# TEC-BVr2.net
KiCad netlist of a schematic drawn in EAGLE
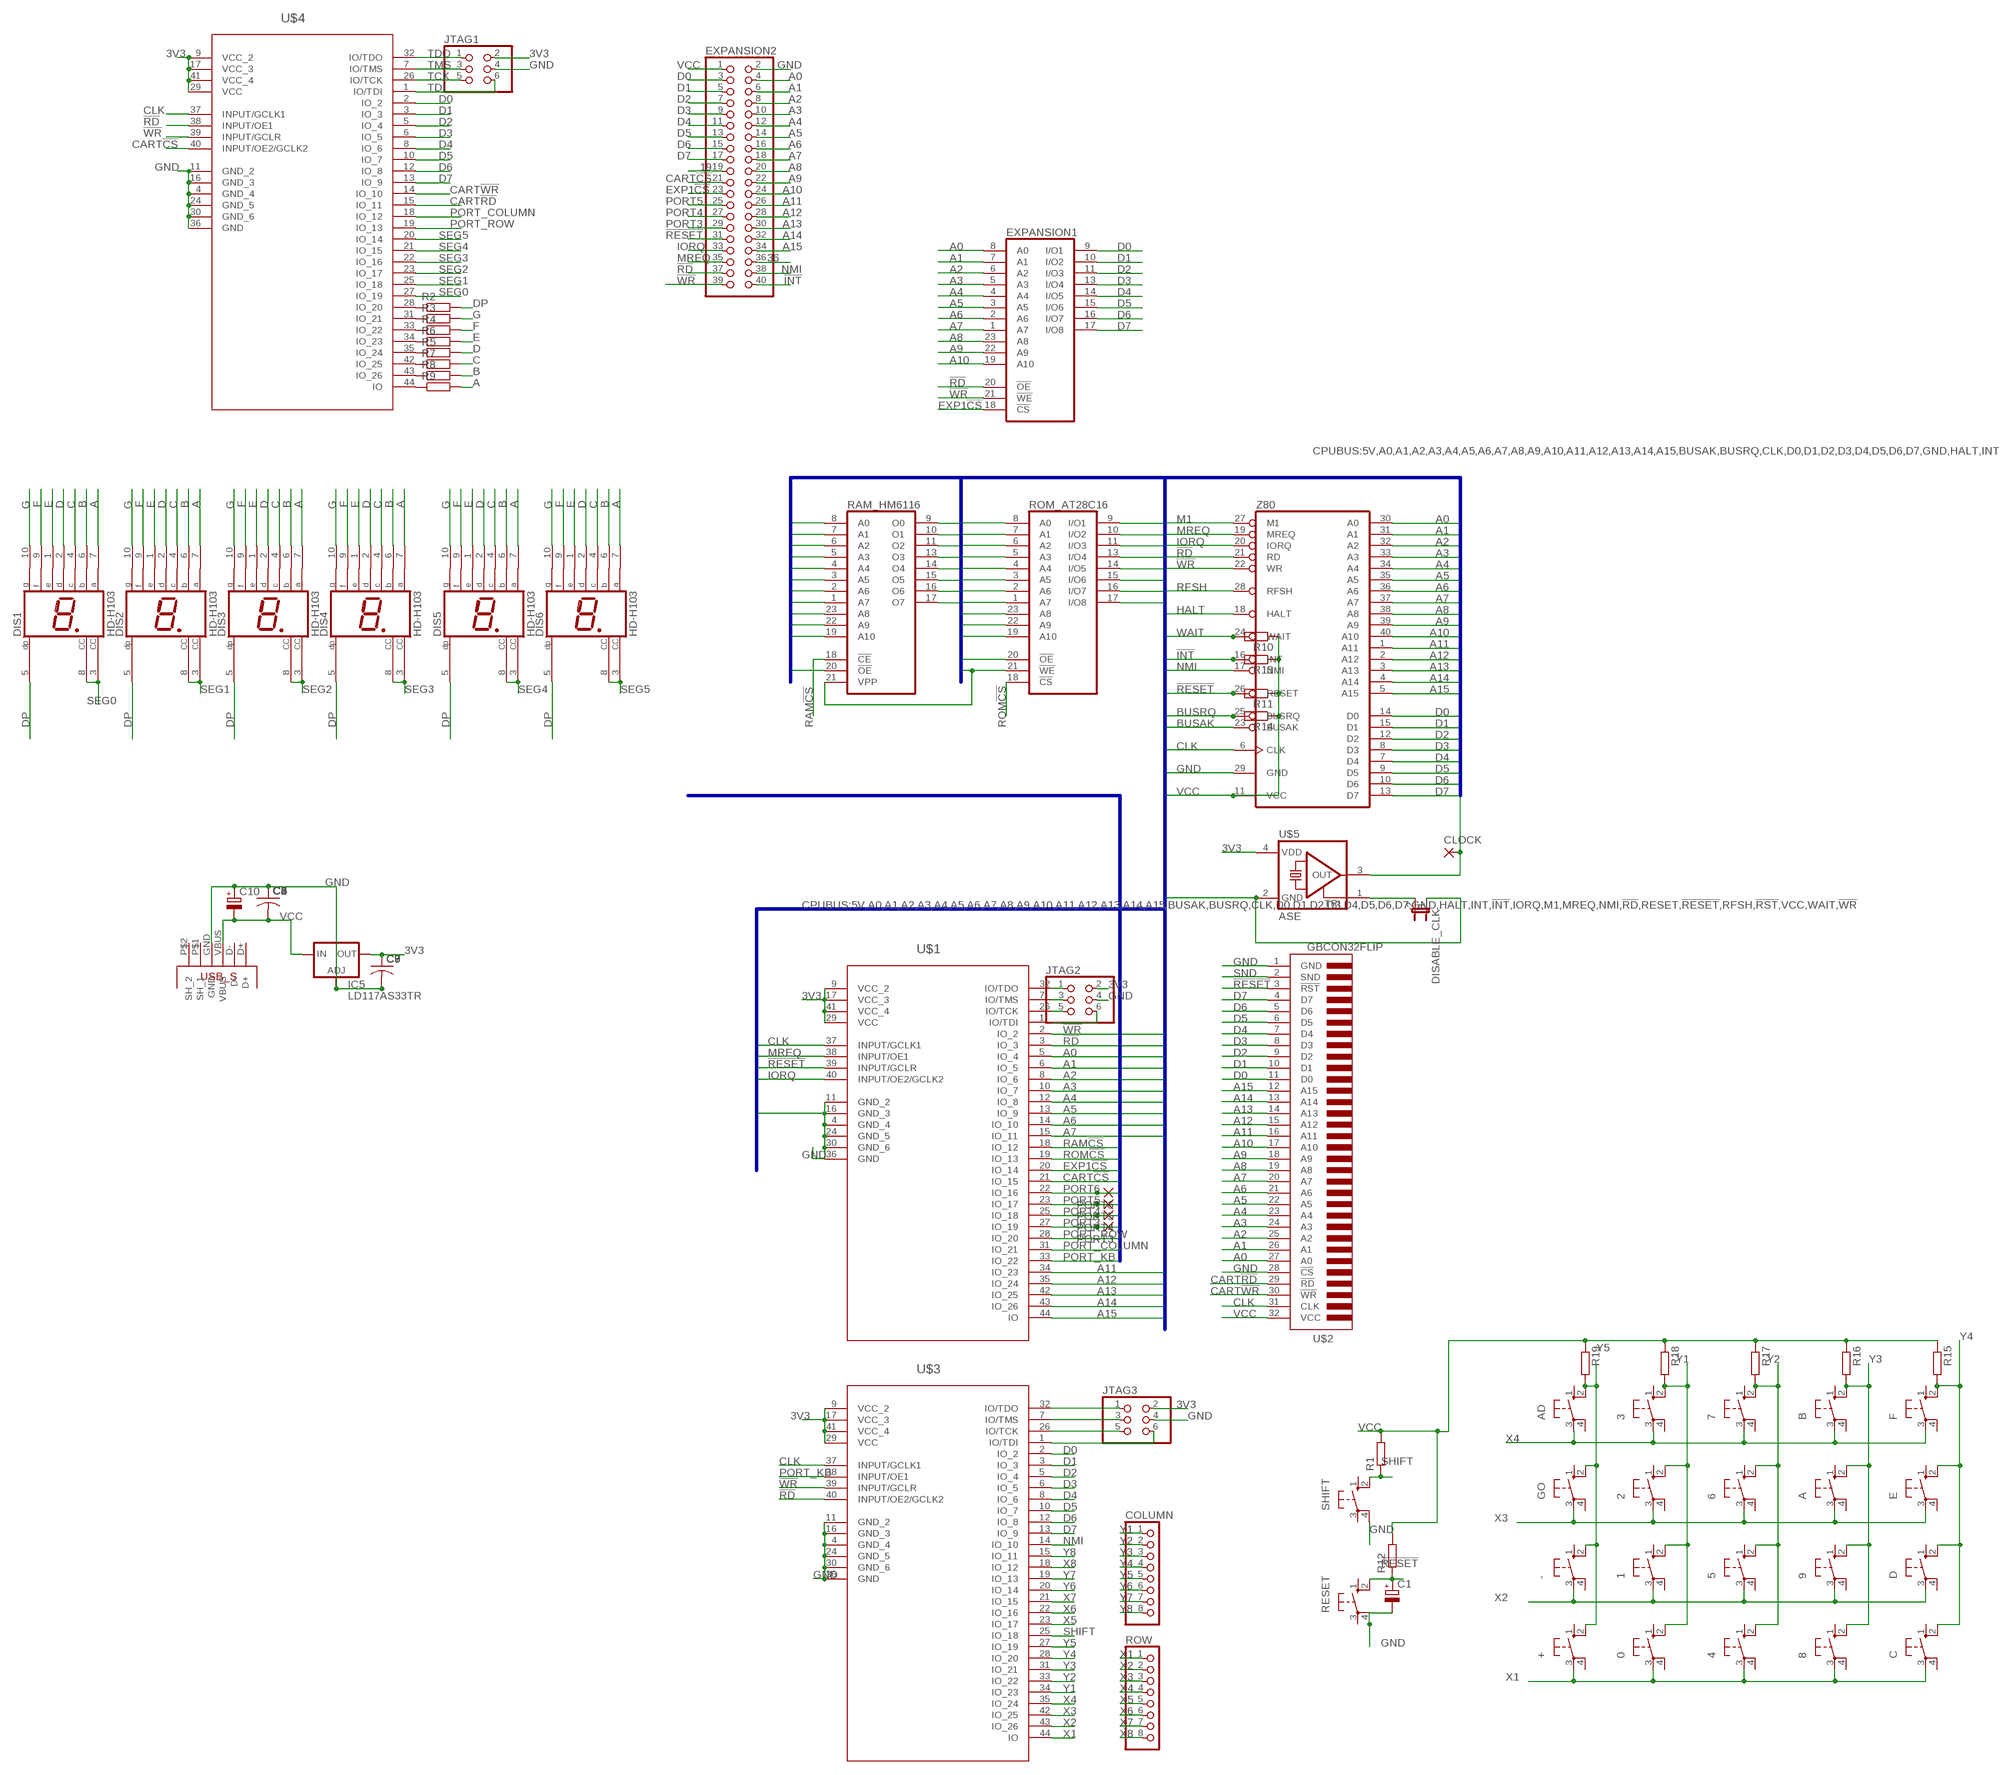
[diagram p0: schematic, sheet 1, part 1 of 2]
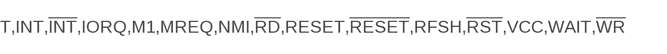
[diagram p1: schematic, sheet 1, part 2 of 2]

(export (version "E")
  (design (tool "Eeschema 10.0.6"))
  (components
    (comp (ref "+")
      (value "10-XX")
      (footprint "eagle-import:B3F-10XX")
      (fields (field (name "MPN") "B3F-1000"))
      (libsource (lib "eagle-import") (part "10-XX"))
    )
    (comp (ref "-")
      (value "10-XX")
      (footprint "eagle-import:B3F-10XX")
      (fields (field (name "MPN") "B3F-1000"))
      (libsource (lib "eagle-import") (part "10-XX"))
    )
    (comp (ref "0")
      (value "10-XX")
      (footprint "eagle-import:B3F-10XX")
      (fields (field (name "MPN") "B3F-1000"))
      (libsource (lib "eagle-import") (part "10-XX"))
    )
    (comp (ref "1")
      (value "10-XX")
      (footprint "eagle-import:B3F-10XX")
      (fields (field (name "MPN") "B3F-1000"))
      (libsource (lib "eagle-import") (part "10-XX"))
    )
    (comp (ref "2")
      (value "10-XX")
      (footprint "eagle-import:B3F-10XX")
      (fields (field (name "MPN") "B3F-1000"))
      (libsource (lib "eagle-import") (part "10-XX"))
    )
    (comp (ref "3")
      (value "10-XX")
      (footprint "eagle-import:B3F-10XX")
      (fields (field (name "MPN") "B3F-1000"))
      (libsource (lib "eagle-import") (part "10-XX"))
    )
    (comp (ref "4")
      (value "10-XX")
      (footprint "eagle-import:B3F-10XX")
      (fields (field (name "MPN") "B3F-1000"))
      (libsource (lib "eagle-import") (part "10-XX"))
    )
    (comp (ref "5")
      (value "10-XX")
      (footprint "eagle-import:B3F-10XX")
      (fields (field (name "MPN") "B3F-1000"))
      (libsource (lib "eagle-import") (part "10-XX"))
    )
    (comp (ref "6")
      (value "10-XX")
      (footprint "eagle-import:B3F-10XX")
      (fields (field (name "MPN") "B3F-1000"))
      (libsource (lib "eagle-import") (part "10-XX"))
    )
    (comp (ref "7")
      (value "10-XX")
      (footprint "eagle-import:B3F-10XX")
      (fields (field (name "MPN") "B3F-1000"))
      (libsource (lib "eagle-import") (part "10-XX"))
    )
    (comp (ref "8")
      (value "10-XX")
      (footprint "eagle-import:B3F-10XX")
      (fields (field (name "MPN") "B3F-1000"))
      (libsource (lib "eagle-import") (part "10-XX"))
    )
    (comp (ref "9")
      (value "10-XX")
      (footprint "eagle-import:B3F-10XX")
      (fields (field (name "MPN") "B3F-1000"))
      (libsource (lib "eagle-import") (part "10-XX"))
    )
    (comp (ref "A")
      (value "10-XX")
      (footprint "eagle-import:B3F-10XX")
      (fields (field (name "MPN") "B3F-1000"))
      (libsource (lib "eagle-import") (part "10-XX"))
    )
    (comp (ref "AD")
      (value "10-XX")
      (footprint "eagle-import:B3F-10XX")
      (fields (field (name "MPN") "B3F-1000"))
      (libsource (lib "eagle-import") (part "10-XX"))
    )
    (comp (ref "B")
      (value "10-XX")
      (footprint "eagle-import:B3F-10XX")
      (fields (field (name "MPN") "B3F-1000"))
      (libsource (lib "eagle-import") (part "10-XX"))
    )
    (comp (ref "C")
      (value "10-XX")
      (footprint "eagle-import:B3F-10XX")
      (fields (field (name "MPN") "B3F-1000"))
      (libsource (lib "eagle-import") (part "10-XX"))
    )
    (comp (ref "C1")
      (value "CPOL-EUE2,5-6E")
      (footprint "eagle-import:E2,5-6E")
      (libsource (lib "eagle-import") (part "CPOL-EUE2,5-6E"))
    )
    (comp (ref "C2")
      (value "C-US050-024X044")
      (footprint "eagle-import:C050-024X044")
      (libsource (lib "eagle-import") (part "C-US050-024X044"))
    )
    (comp (ref "C3")
      (value "C-US050-024X044")
      (footprint "eagle-import:C050-024X044")
      (libsource (lib "eagle-import") (part "C-US050-024X044"))
    )
    (comp (ref "C4")
      (value "C-US050-024X044")
      (footprint "eagle-import:C050-024X044")
      (libsource (lib "eagle-import") (part "C-US050-024X044"))
    )
    (comp (ref "C5")
      (value "C-US050-024X044")
      (footprint "eagle-import:C050-024X044")
      (libsource (lib "eagle-import") (part "C-US050-024X044"))
    )
    (comp (ref "C6")
      (value "C-US050-024X044")
      (footprint "eagle-import:C050-024X044")
      (libsource (lib "eagle-import") (part "C-US050-024X044"))
    )
    (comp (ref "C7")
      (value "C-US050-024X044")
      (footprint "eagle-import:C050-024X044")
      (libsource (lib "eagle-import") (part "C-US050-024X044"))
    )
    (comp (ref "C8")
      (value "C-US050-024X044")
      (footprint "eagle-import:C050-024X044")
      (libsource (lib "eagle-import") (part "C-US050-024X044"))
    )
    (comp (ref "C9")
      (value "C-US050-024X044")
      (footprint "eagle-import:C050-024X044")
      (libsource (lib "eagle-import") (part "C-US050-024X044"))
    )
    (comp (ref "C10")
      (value "CPOL-EUE2,5-6E")
      (footprint "eagle-import:E2,5-6E")
      (libsource (lib "eagle-import") (part "CPOL-EUE2,5-6E"))
    )
    (comp (ref "CLOCK")
      (value "1,6/0,8")
      (footprint "eagle-import:1,6_0,8")
      (libsource (lib "eagle-import") (part "1,6/0,8"))
    )
    (comp (ref "COLUMN")
      (value "PINHD-1X8")
      (footprint "eagle-import:1X08")
      (libsource (lib "eagle-import") (part "PINHD-1X8"))
    )
    (comp (ref "D")
      (value "10-XX")
      (footprint "eagle-import:B3F-10XX")
      (fields (field (name "MPN") "B3F-1000"))
      (libsource (lib "eagle-import") (part "10-XX"))
    )
    (comp (ref "DIS1")
      (value "HD-H103")
      (footprint "eagle-import:HDSP-M")
      (libsource (lib "eagle-import") (part "HD-H103"))
    )
    (comp (ref "DIS2")
      (value "HD-H103")
      (footprint "eagle-import:HDSP-M")
      (libsource (lib "eagle-import") (part "HD-H103"))
    )
    (comp (ref "DIS3")
      (value "HD-H103")
      (footprint "eagle-import:HDSP-M")
      (libsource (lib "eagle-import") (part "HD-H103"))
    )
    (comp (ref "DIS4")
      (value "HD-H103")
      (footprint "eagle-import:HDSP-M")
      (libsource (lib "eagle-import") (part "HD-H103"))
    )
    (comp (ref "DIS5")
      (value "HD-H103")
      (footprint "eagle-import:HDSP-M")
      (libsource (lib "eagle-import") (part "HD-H103"))
    )
    (comp (ref "DIS6")
      (value "HD-H103")
      (footprint "eagle-import:HDSP-M")
      (libsource (lib "eagle-import") (part "HD-H103"))
    )
    (comp (ref "DISABLE_CLK")
      (value "JP1E")
      (footprint "eagle-import:JP1")
      (libsource (lib "eagle-import") (part "JP1E"))
    )
    (comp (ref "E")
      (value "10-XX")
      (footprint "eagle-import:B3F-10XX")
      (fields (field (name "MPN") "B3F-1000"))
      (libsource (lib "eagle-import") (part "10-XX"))
    )
    (comp (ref "EXPANSION1")
      (value "6116P")
      (footprint "eagle-import:DIL24-6")
      (libsource (lib "eagle-import") (part "6116P"))
    )
    (comp (ref "EXPANSION2")
      (value "PINHD-2X20")
      (footprint "eagle-import:2X20")
      (libsource (lib "eagle-import") (part "PINHD-2X20"))
    )
    (comp (ref "F")
      (value "10-XX")
      (footprint "eagle-import:B3F-10XX")
      (fields (field (name "MPN") "B3F-1000"))
      (libsource (lib "eagle-import") (part "10-XX"))
    )
    (comp (ref "GO")
      (value "10-XX")
      (footprint "eagle-import:B3F-10XX")
      (fields (field (name "MPN") "B3F-1000"))
      (libsource (lib "eagle-import") (part "10-XX"))
    )
    (comp (ref "IC5")
      (value "LD117AS33TR")
      (footprint "eagle-import:SOT223")
      (libsource (lib "eagle-import") (part "LD117A?S33TR"))
    )
    (comp (ref "JTAG1")
      (value "PINHD-2X3")
      (footprint "eagle-import:2X03")
      (libsource (lib "eagle-import") (part "PINHD-2X3"))
    )
    (comp (ref "JTAG2")
      (value "PINHD-2X3")
      (footprint "eagle-import:2X03")
      (libsource (lib "eagle-import") (part "PINHD-2X3"))
    )
    (comp (ref "JTAG3")
      (value "PINHD-2X3")
      (footprint "eagle-import:2X03")
      (libsource (lib "eagle-import") (part "PINHD-2X3"))
    )
    (comp (ref "PORT3")
      (value "1,6/0,8")
      (footprint "eagle-import:1,6_0,8")
      (libsource (lib "eagle-import") (part "1,6/0,8"))
    )
    (comp (ref "PORT4")
      (value "1,6/0,8")
      (footprint "eagle-import:1,6_0,8")
      (libsource (lib "eagle-import") (part "1,6/0,8"))
    )
    (comp (ref "PORT5")
      (value "1,6/0,8")
      (footprint "eagle-import:1,6_0,8")
      (libsource (lib "eagle-import") (part "1,6/0,8"))
    )
    (comp (ref "PORT6")
      (value "1,6/0,8")
      (footprint "eagle-import:1,6_0,8")
      (libsource (lib "eagle-import") (part "1,6/0,8"))
    )
    (comp (ref "R1")
      (value "R-EU_0207/12")
      (footprint "eagle-import:0207_12")
      (libsource (lib "eagle-import") (part "R-EU_0207/12"))
    )
    (comp (ref "R2")
      (value "R-EU_0207/12")
      (footprint "eagle-import:0207_12")
      (libsource (lib "eagle-import") (part "R-EU_0207/12"))
    )
    (comp (ref "R3")
      (value "R-EU_0207/12")
      (footprint "eagle-import:0207_12")
      (libsource (lib "eagle-import") (part "R-EU_0207/12"))
    )
    (comp (ref "R4")
      (value "R-EU_0207/12")
      (footprint "eagle-import:0207_12")
      (libsource (lib "eagle-import") (part "R-EU_0207/12"))
    )
    (comp (ref "R5")
      (value "R-EU_0207/12")
      (footprint "eagle-import:0207_12")
      (libsource (lib "eagle-import") (part "R-EU_0207/12"))
    )
    (comp (ref "R6")
      (value "R-EU_0207/12")
      (footprint "eagle-import:0207_12")
      (libsource (lib "eagle-import") (part "R-EU_0207/12"))
    )
    (comp (ref "R7")
      (value "R-EU_0207/12")
      (footprint "eagle-import:0207_12")
      (libsource (lib "eagle-import") (part "R-EU_0207/12"))
    )
    (comp (ref "R8")
      (value "R-EU_0207/12")
      (footprint "eagle-import:0207_12")
      (libsource (lib "eagle-import") (part "R-EU_0207/12"))
    )
    (comp (ref "R9")
      (value "R-EU_0207/12")
      (footprint "eagle-import:0207_12")
      (libsource (lib "eagle-import") (part "R-EU_0207/12"))
    )
    (comp (ref "R10")
      (value "R-EU_0207/12")
      (footprint "eagle-import:0207_12")
      (libsource (lib "eagle-import") (part "R-EU_0207/12"))
    )
    (comp (ref "R11")
      (value "R-EU_0207/12")
      (footprint "eagle-import:0207_12")
      (libsource (lib "eagle-import") (part "R-EU_0207/12"))
    )
    (comp (ref "R12")
      (value "R-EU_0207/12")
      (footprint "eagle-import:0207_12")
      (libsource (lib "eagle-import") (part "R-EU_0207/12"))
    )
    (comp (ref "R13")
      (value "R-EU_0207/12")
      (footprint "eagle-import:0207_12")
      (libsource (lib "eagle-import") (part "R-EU_0207/12"))
    )
    (comp (ref "R14")
      (value "R-EU_0207/12")
      (footprint "eagle-import:0207_12")
      (libsource (lib "eagle-import") (part "R-EU_0207/12"))
    )
    (comp (ref "R15")
      (value "R-EU_0204/7")
      (footprint "eagle-import:0204_7")
      (libsource (lib "eagle-import") (part "R-EU_0204/7"))
    )
    (comp (ref "R16")
      (value "R-EU_0204/7")
      (footprint "eagle-import:0204_7")
      (libsource (lib "eagle-import") (part "R-EU_0204/7"))
    )
    (comp (ref "R17")
      (value "R-EU_0204/7")
      (footprint "eagle-import:0204_7")
      (libsource (lib "eagle-import") (part "R-EU_0204/7"))
    )
    (comp (ref "R18")
      (value "R-EU_0204/7")
      (footprint "eagle-import:0204_7")
      (libsource (lib "eagle-import") (part "R-EU_0204/7"))
    )
    (comp (ref "R19")
      (value "R-EU_0204/7")
      (footprint "eagle-import:0204_7")
      (libsource (lib "eagle-import") (part "R-EU_0204/7"))
    )
    (comp (ref "RAM_HM6116")
      (value "2716")
      (footprint "eagle-import:DIL24")
      (libsource (lib "eagle-import") (part "2716"))
    )
    (comp (ref "RESET")
      (value "10-XX")
      (footprint "eagle-import:B3F-10XX")
      (fields (field (name "MPN") "B3F-1000"))
      (libsource (lib "eagle-import") (part "10-XX"))
    )
    (comp (ref "ROM_AT28C16")
      (value "6116P")
      (footprint "eagle-import:DIL24-6")
      (libsource (lib "eagle-import") (part "6116P"))
    )
    (comp (ref "ROW")
      (value "PINHD-1X8")
      (footprint "eagle-import:1X08")
      (libsource (lib "eagle-import") (part "PINHD-1X8"))
    )
    (comp (ref "SHIFT")
      (value "10-XX")
      (footprint "eagle-import:B3F-10XX")
      (fields (field (name "MPN") "B3F-1000"))
      (libsource (lib "eagle-import") (part "10-XX"))
    )
    (comp (ref "U$1")
      (value "Address Decoding")
      (footprint "eagle-import:QFP80P1200X1200X120-44N")
      (fields (field (name "MPN") "EPM3064ATC44-10N"))
      (libsource (lib "eagle-import") (part "EPM3064ATC44-10N"))
    )
    (comp (ref "U$2")
      (value "GBCON32FLIP")
      (footprint "eagle-import:GB_CON32")
      (libsource (lib "eagle-import") (part "GBCON32FLIP"))
    )
    (comp (ref "U$3")
      (value "Keyboard Decoding")
      (footprint "eagle-import:QFP80P1200X1200X120-44N")
      (fields (field (name "MPN") "EPM3064ATC44-10N"))
      (libsource (lib "eagle-import") (part "EPM3064ATC44-10N"))
    )
    (comp (ref "U$4")
      (value "Display Decoding")
      (footprint "eagle-import:QFP80P1200X1200X120-44N")
      (fields (field (name "MPN") "EPM3064ATC44-10N"))
      (libsource (lib "eagle-import") (part "EPM3064ATC44-10N"))
    )
    (comp (ref "U$5")
      (value "ASE")
      (footprint "eagle-import:ASE")
      (libsource (lib "eagle-import") (part "ASE"))
    )
    (comp (ref "U$6")
      (value "USB")
      (footprint "eagle-import:USB_B_PTH")
      (libsource (lib "eagle-import") (part "USB"))
    )
    (comp (ref "Z80")
      (value "Z80CPU")
      (footprint "eagle-import:DIL40")
      (libsource (lib "eagle-import") (part "Z80CPU"))
    )
  )
  (nets
    (net (code "5") (name "/3V3") (class "Default")
      (node (ref "C7") (pin "1") (pinfunction "1_1") (pintype "passive"))
      (node (ref "C8") (pin "1") (pinfunction "1_1") (pintype "passive"))
      (node (ref "C9") (pin "1") (pinfunction "1_1") (pintype "passive"))
      (node (ref "IC5") (pin "4") (pinfunction "OUT_4") (pintype "passive"))
      (node (ref "JTAG1") (pin "2") (pinfunction "2_2") (pintype "passive"))
      (node (ref "JTAG2") (pin "2") (pinfunction "2_2") (pintype "passive"))
      (node (ref "JTAG3") (pin "2") (pinfunction "2_2") (pintype "passive"))
      (node (ref "U$1") (pin "17") (pinfunction "VCC_3_17") (pintype "power_in"))
      (node (ref "U$1") (pin "29") (pinfunction "VCC_29") (pintype "power_in"))
      (node (ref "U$1") (pin "41") (pinfunction "VCC_4_41") (pintype "power_in"))
      (node (ref "U$1") (pin "9") (pinfunction "VCC_2_9") (pintype "power_in"))
      (node (ref "U$3") (pin "17") (pinfunction "VCC_3_17") (pintype "power_in"))
      (node (ref "U$3") (pin "29") (pinfunction "VCC_29") (pintype "power_in"))
      (node (ref "U$3") (pin "41") (pinfunction "VCC_4_41") (pintype "power_in"))
      (node (ref "U$3") (pin "9") (pinfunction "VCC_2_9") (pintype "power_in"))
      (node (ref "U$4") (pin "17") (pinfunction "VCC_3_17") (pintype "power_in"))
      (node (ref "U$4") (pin "29") (pinfunction "VCC_29") (pintype "power_in"))
      (node (ref "U$4") (pin "41") (pinfunction "VCC_4_41") (pintype "power_in"))
      (node (ref "U$4") (pin "9") (pinfunction "VCC_2_9") (pintype "power_in"))
      (node (ref "U$5") (pin "4") (pinfunction "VDD_4") (pintype "power_in"))
    )
    (net (code "6") (name "/19") (class "Default")
      (node (ref "EXPANSION2") (pin "19") (pinfunction "19_19") (pintype "passive"))
    )
    (net (code "7") (name "/36") (class "Default")
      (node (ref "EXPANSION2") (pin "36") (pinfunction "36_36") (pintype "passive"))
    )
    (net (code "8") (name "/A") (class "Default")
      (node (ref "DIS1") (pin "7") (pinfunction "A_7") (pintype "passive"))
      (node (ref "DIS2") (pin "7") (pinfunction "A_7") (pintype "passive"))
      (node (ref "DIS3") (pin "7") (pinfunction "A_7") (pintype "passive"))
      (node (ref "DIS4") (pin "7") (pinfunction "A_7") (pintype "passive"))
      (node (ref "DIS5") (pin "7") (pinfunction "A_7") (pintype "passive"))
      (node (ref "DIS6") (pin "7") (pinfunction "A_7") (pintype "passive"))
      (node (ref "R9") (pin "2") (pinfunction "2_2") (pintype "passive"))
    )
    (net (code "9") (name "/A0") (class "Default")
      (node (ref "EXPANSION1") (pin "8") (pinfunction "A0_8") (pintype "input"))
      (node (ref "EXPANSION2") (pin "4") (pinfunction "4_4") (pintype "passive"))
      (node (ref "RAM_HM6116") (pin "8") (pinfunction "A0_8") (pintype "input"))
      (node (ref "ROM_AT28C16") (pin "8") (pinfunction "A0_8") (pintype "input"))
      (node (ref "U$1") (pin "5") (pinfunction "IO_4_5") (pintype "bidirectional"))
      (node (ref "U$2") (pin "27") (pinfunction "A0_27") (pintype "input"))
      (node (ref "Z80") (pin "30") (pinfunction "A0_30") (pintype "output"))
    )
    (net (code "10") (name "/A1") (class "Default")
      (node (ref "EXPANSION1") (pin "7") (pinfunction "A1_7") (pintype "input"))
      (node (ref "EXPANSION2") (pin "6") (pinfunction "6_6") (pintype "passive"))
      (node (ref "RAM_HM6116") (pin "7") (pinfunction "A1_7") (pintype "input"))
      (node (ref "ROM_AT28C16") (pin "7") (pinfunction "A1_7") (pintype "input"))
      (node (ref "U$1") (pin "6") (pinfunction "IO_5_6") (pintype "bidirectional"))
      (node (ref "U$2") (pin "26") (pinfunction "A1_26") (pintype "input"))
      (node (ref "Z80") (pin "31") (pinfunction "A1_31") (pintype "output"))
    )
    (net (code "11") (name "/A2") (class "Default")
      (node (ref "EXPANSION1") (pin "6") (pinfunction "A2_6") (pintype "input"))
      (node (ref "EXPANSION2") (pin "8") (pinfunction "8_8") (pintype "passive"))
      (node (ref "RAM_HM6116") (pin "6") (pinfunction "A2_6") (pintype "input"))
      (node (ref "ROM_AT28C16") (pin "6") (pinfunction "A2_6") (pintype "input"))
      (node (ref "U$1") (pin "8") (pinfunction "IO_6_8") (pintype "bidirectional"))
      (node (ref "U$2") (pin "25") (pinfunction "A2_25") (pintype "input"))
      (node (ref "Z80") (pin "32") (pinfunction "A2_32") (pintype "output"))
    )
    (net (code "12") (name "/A3") (class "Default")
      (node (ref "EXPANSION1") (pin "5") (pinfunction "A3_5") (pintype "input"))
      (node (ref "EXPANSION2") (pin "10") (pinfunction "10_10") (pintype "passive"))
      (node (ref "RAM_HM6116") (pin "5") (pinfunction "A3_5") (pintype "input"))
      (node (ref "ROM_AT28C16") (pin "5") (pinfunction "A3_5") (pintype "input"))
      (node (ref "U$1") (pin "10") (pinfunction "IO_7_10") (pintype "bidirectional"))
      (node (ref "U$2") (pin "24") (pinfunction "A3_24") (pintype "input"))
      (node (ref "Z80") (pin "33") (pinfunction "A3_33") (pintype "output"))
    )
    (net (code "13") (name "/A4") (class "Default")
      (node (ref "EXPANSION1") (pin "4") (pinfunction "A4_4") (pintype "input"))
      (node (ref "EXPANSION2") (pin "12") (pinfunction "12_12") (pintype "passive"))
      (node (ref "RAM_HM6116") (pin "4") (pinfunction "A4_4") (pintype "input"))
      (node (ref "ROM_AT28C16") (pin "4") (pinfunction "A4_4") (pintype "input"))
      (node (ref "U$1") (pin "12") (pinfunction "IO_8_12") (pintype "bidirectional"))
      (node (ref "U$2") (pin "23") (pinfunction "A4_23") (pintype "input"))
      (node (ref "Z80") (pin "34") (pinfunction "A4_34") (pintype "output"))
    )
    (net (code "14") (name "/A5") (class "Default")
      (node (ref "EXPANSION1") (pin "3") (pinfunction "A5_3") (pintype "input"))
      (node (ref "EXPANSION2") (pin "14") (pinfunction "14_14") (pintype "passive"))
      (node (ref "RAM_HM6116") (pin "3") (pinfunction "A5_3") (pintype "input"))
      (node (ref "ROM_AT28C16") (pin "3") (pinfunction "A5_3") (pintype "input"))
      (node (ref "U$1") (pin "13") (pinfunction "IO_9_13") (pintype "bidirectional"))
      (node (ref "U$2") (pin "22") (pinfunction "A5_22") (pintype "input"))
      (node (ref "Z80") (pin "35") (pinfunction "A5_35") (pintype "output"))
    )
    (net (code "15") (name "/A6") (class "Default")
      (node (ref "EXPANSION1") (pin "2") (pinfunction "A6_2") (pintype "input"))
      (node (ref "EXPANSION2") (pin "16") (pinfunction "16_16") (pintype "passive"))
      (node (ref "RAM_HM6116") (pin "2") (pinfunction "A6_2") (pintype "input"))
      (node (ref "ROM_AT28C16") (pin "2") (pinfunction "A6_2") (pintype "input"))
      (node (ref "U$1") (pin "14") (pinfunction "IO_10_14") (pintype "bidirectional"))
      (node (ref "U$2") (pin "21") (pinfunction "A6_21") (pintype "input"))
      (node (ref "Z80") (pin "36") (pinfunction "A6_36") (pintype "output"))
    )
    (net (code "16") (name "/A7") (class "Default")
      (node (ref "EXPANSION1") (pin "1") (pinfunction "A7_1") (pintype "input"))
      (node (ref "EXPANSION2") (pin "18") (pinfunction "18_18") (pintype "passive"))
      (node (ref "RAM_HM6116") (pin "1") (pinfunction "A7_1") (pintype "input"))
      (node (ref "ROM_AT28C16") (pin "1") (pinfunction "A7_1") (pintype "input"))
      (node (ref "U$1") (pin "15") (pinfunction "IO_11_15") (pintype "bidirectional"))
      (node (ref "U$2") (pin "20") (pinfunction "A7_20") (pintype "input"))
      (node (ref "Z80") (pin "37") (pinfunction "A7_37") (pintype "output"))
    )
    (net (code "17") (name "/A8") (class "Default")
      (node (ref "EXPANSION1") (pin "23") (pinfunction "A8_23") (pintype "input"))
      (node (ref "EXPANSION2") (pin "20") (pinfunction "20_20") (pintype "passive"))
      (node (ref "RAM_HM6116") (pin "23") (pinfunction "A8_23") (pintype "input"))
      (node (ref "ROM_AT28C16") (pin "23") (pinfunction "A8_23") (pintype "input"))
      (node (ref "U$2") (pin "19") (pinfunction "A8_19") (pintype "input"))
      (node (ref "Z80") (pin "38") (pinfunction "A8_38") (pintype "output"))
    )
    (net (code "18") (name "/A9") (class "Default")
      (node (ref "EXPANSION1") (pin "22") (pinfunction "A9_22") (pintype "input"))
      (node (ref "EXPANSION2") (pin "22") (pinfunction "22_22") (pintype "passive"))
      (node (ref "RAM_HM6116") (pin "22") (pinfunction "A9_22") (pintype "input"))
      (node (ref "ROM_AT28C16") (pin "22") (pinfunction "A9_22") (pintype "input"))
      (node (ref "U$2") (pin "18") (pinfunction "A9_18") (pintype "input"))
      (node (ref "Z80") (pin "39") (pinfunction "A9_39") (pintype "output"))
    )
    (net (code "19") (name "/A10") (class "Default")
      (node (ref "EXPANSION1") (pin "19") (pinfunction "A10_19") (pintype "input"))
      (node (ref "EXPANSION2") (pin "24") (pinfunction "24_24") (pintype "passive"))
      (node (ref "RAM_HM6116") (pin "19") (pinfunction "A10_19") (pintype "input"))
      (node (ref "ROM_AT28C16") (pin "19") (pinfunction "A10_19") (pintype "input"))
      (node (ref "U$2") (pin "17") (pinfunction "A10_17") (pintype "input"))
      (node (ref "Z80") (pin "40") (pinfunction "A10_40") (pintype "output"))
    )
    (net (code "20") (name "/A11") (class "Default")
      (node (ref "EXPANSION2") (pin "26") (pinfunction "26_26") (pintype "passive"))
      (node (ref "U$1") (pin "34") (pinfunction "IO_23_34") (pintype "bidirectional"))
      (node (ref "U$2") (pin "16") (pinfunction "A11_16") (pintype "input"))
      (node (ref "Z80") (pin "1") (pinfunction "A11_1") (pintype "output"))
    )
    (net (code "21") (name "/A12") (class "Default")
      (node (ref "EXPANSION2") (pin "28") (pinfunction "28_28") (pintype "passive"))
      (node (ref "U$1") (pin "35") (pinfunction "IO_24_35") (pintype "bidirectional"))
      (node (ref "U$2") (pin "15") (pinfunction "A12_15") (pintype "input"))
      (node (ref "Z80") (pin "2") (pinfunction "A12_2") (pintype "output"))
    )
    (net (code "22") (name "/A13") (class "Default")
      (node (ref "EXPANSION2") (pin "30") (pinfunction "30_30") (pintype "passive"))
      (node (ref "U$1") (pin "42") (pinfunction "IO_25_42") (pintype "bidirectional"))
      (node (ref "U$2") (pin "14") (pinfunction "A13_14") (pintype "input"))
      (node (ref "Z80") (pin "3") (pinfunction "A13_3") (pintype "output"))
    )
    (net (code "23") (name "/A14") (class "Default")
      (node (ref "EXPANSION2") (pin "32") (pinfunction "32_32") (pintype "passive"))
      (node (ref "U$1") (pin "43") (pinfunction "IO_26_43") (pintype "bidirectional"))
      (node (ref "U$2") (pin "13") (pinfunction "A14_13") (pintype "input"))
      (node (ref "Z80") (pin "4") (pinfunction "A14_4") (pintype "output"))
    )
    (net (code "24") (name "/A15") (class "Default")
      (node (ref "EXPANSION2") (pin "34") (pinfunction "34_34") (pintype "passive"))
      (node (ref "U$1") (pin "44") (pinfunction "IO_44") (pintype "bidirectional"))
      (node (ref "U$2") (pin "12") (pinfunction "A15_12") (pintype "input"))
      (node (ref "Z80") (pin "5") (pinfunction "A15_5") (pintype "output"))
    )
    (net (code "25") (name "/B") (class "Default")
      (node (ref "DIS1") (pin "6") (pinfunction "B_6") (pintype "passive"))
      (node (ref "DIS2") (pin "6") (pinfunction "B_6") (pintype "passive"))
      (node (ref "DIS3") (pin "6") (pinfunction "B_6") (pintype "passive"))
      (node (ref "DIS4") (pin "6") (pinfunction "B_6") (pintype "passive"))
      (node (ref "DIS5") (pin "6") (pinfunction "B_6") (pintype "passive"))
      (node (ref "DIS6") (pin "6") (pinfunction "B_6") (pintype "passive"))
      (node (ref "R8") (pin "2") (pinfunction "2_2") (pintype "passive"))
    )
    (net (code "26") (name "/BUSAK") (class "Default")
      (node (ref "Z80") (pin "23") (pinfunction "BUSAK_23") (pintype "output"))
    )
    (net (code "27") (name "/BUSRQ") (class "Default")
      (node (ref "R14") (pin "2") (pinfunction "2_2") (pintype "passive"))
      (node (ref "Z80") (pin "25") (pinfunction "BUSRQ_25") (pintype "input"))
    )
    (net (code "28") (name "/C") (class "Default")
      (node (ref "DIS1") (pin "4") (pinfunction "C_4") (pintype "passive"))
      (node (ref "DIS2") (pin "4") (pinfunction "C_4") (pintype "passive"))
      (node (ref "DIS3") (pin "4") (pinfunction "C_4") (pintype "passive"))
      (node (ref "DIS4") (pin "4") (pinfunction "C_4") (pintype "passive"))
      (node (ref "DIS5") (pin "4") (pinfunction "C_4") (pintype "passive"))
      (node (ref "DIS6") (pin "4") (pinfunction "C_4") (pintype "passive"))
      (node (ref "R7") (pin "2") (pinfunction "2_2") (pintype "passive"))
    )
    (net (code "29") (name "/CART~{CS}") (class "Default")
      (node (ref "EXPANSION2") (pin "21") (pinfunction "21_21") (pintype "passive"))
      (node (ref "U$1") (pin "21") (pinfunction "IO_15_21") (pintype "bidirectional"))
      (node (ref "U$4") (pin "40") (pinfunction "INPUT/OE2/GCLK2_40") (pintype "input"))
    )
    (net (code "30") (name "/CART~{RD}") (class "Default")
      (node (ref "U$2") (pin "29") (pinfunction "~{RD}_29") (pintype "input"))
      (node (ref "U$4") (pin "15") (pinfunction "IO_11_15") (pintype "bidirectional"))
    )
    (net (code "31") (name "/CART~{WR}") (class "Default")
      (node (ref "U$2") (pin "30") (pinfunction "~{WR}_30") (pintype "input"))
      (node (ref "U$4") (pin "14") (pinfunction "IO_10_14") (pintype "bidirectional"))
    )
    (net (code "32") (name "/CLK") (class "Default")
      (node (ref "CLOCK") (pin "1") (pinfunction "P_1") (pintype "passive"))
      (node (ref "U$1") (pin "37") (pinfunction "INPUT/GCLK1_37") (pintype "input"))
      (node (ref "U$2") (pin "31") (pinfunction "CLK_31") (pintype "input"))
      (node (ref "U$3") (pin "37") (pinfunction "INPUT/GCLK1_37") (pintype "input"))
      (node (ref "U$4") (pin "37") (pinfunction "INPUT/GCLK1_37") (pintype "input"))
      (node (ref "U$5") (pin "3") (pinfunction "OUT_3") (pintype "output"))
      (node (ref "Z80") (pin "6") (pinfunction "CLK_6") (pintype "input"))
    )
    (net (code "33") (name "/D") (class "Default")
      (node (ref "DIS1") (pin "2") (pinfunction "D_2") (pintype "passive"))
      (node (ref "DIS2") (pin "2") (pinfunction "D_2") (pintype "passive"))
      (node (ref "DIS3") (pin "2") (pinfunction "D_2") (pintype "passive"))
      (node (ref "DIS4") (pin "2") (pinfunction "D_2") (pintype "passive"))
      (node (ref "DIS5") (pin "2") (pinfunction "D_2") (pintype "passive"))
      (node (ref "DIS6") (pin "2") (pinfunction "D_2") (pintype "passive"))
      (node (ref "R5") (pin "2") (pinfunction "2_2") (pintype "passive"))
    )
    (net (code "34") (name "/D0") (class "Default")
      (node (ref "EXPANSION1") (pin "9") (pinfunction "I/O1_9") (pintype "bidirectional"))
      (node (ref "EXPANSION2") (pin "3") (pinfunction "3_3") (pintype "passive"))
      (node (ref "RAM_HM6116") (pin "9") (pinfunction "O0_9") (pintype "tri_state"))
      (node (ref "ROM_AT28C16") (pin "9") (pinfunction "I/O1_9") (pintype "bidirectional"))
      (node (ref "U$2") (pin "11") (pinfunction "D0_11") (pintype "bidirectional"))
      (node (ref "U$3") (pin "2") (pinfunction "IO_2_2") (pintype "bidirectional"))
      (node (ref "U$4") (pin "2") (pinfunction "IO_2_2") (pintype "bidirectional"))
      (node (ref "Z80") (pin "14") (pinfunction "D0_14") (pintype "bidirectional"))
    )
    (net (code "35") (name "/D1") (class "Default")
      (node (ref "EXPANSION1") (pin "10") (pinfunction "I/O2_10") (pintype "bidirectional"))
      (node (ref "EXPANSION2") (pin "5") (pinfunction "5_5") (pintype "passive"))
      (node (ref "RAM_HM6116") (pin "10") (pinfunction "O1_10") (pintype "tri_state"))
      (node (ref "ROM_AT28C16") (pin "10") (pinfunction "I/O2_10") (pintype "bidirectional"))
      (node (ref "U$2") (pin "10") (pinfunction "D1_10") (pintype "bidirectional"))
      (node (ref "U$3") (pin "3") (pinfunction "IO_3_3") (pintype "bidirectional"))
      (node (ref "U$4") (pin "3") (pinfunction "IO_3_3") (pintype "bidirectional"))
      (node (ref "Z80") (pin "15") (pinfunction "D1_15") (pintype "bidirectional"))
    )
    (net (code "36") (name "/D2") (class "Default")
      (node (ref "EXPANSION1") (pin "11") (pinfunction "I/O3_11") (pintype "bidirectional"))
      (node (ref "EXPANSION2") (pin "7") (pinfunction "7_7") (pintype "passive"))
      (node (ref "RAM_HM6116") (pin "11") (pinfunction "O2_11") (pintype "tri_state"))
      (node (ref "ROM_AT28C16") (pin "11") (pinfunction "I/O3_11") (pintype "bidirectional"))
      (node (ref "U$2") (pin "9") (pinfunction "D2_9") (pintype "bidirectional"))
      (node (ref "U$3") (pin "5") (pinfunction "IO_4_5") (pintype "bidirectional"))
      (node (ref "U$4") (pin "5") (pinfunction "IO_4_5") (pintype "bidirectional"))
      (node (ref "Z80") (pin "12") (pinfunction "D2_12") (pintype "bidirectional"))
    )
    (net (code "37") (name "/D3") (class "Default")
      (node (ref "EXPANSION1") (pin "13") (pinfunction "I/O4_13") (pintype "bidirectional"))
      (node (ref "EXPANSION2") (pin "9") (pinfunction "9_9") (pintype "passive"))
      (node (ref "RAM_HM6116") (pin "13") (pinfunction "O3_13") (pintype "tri_state"))
      (node (ref "ROM_AT28C16") (pin "13") (pinfunction "I/O4_13") (pintype "bidirectional"))
      (node (ref "U$2") (pin "8") (pinfunction "D3_8") (pintype "bidirectional"))
      (node (ref "U$3") (pin "6") (pinfunction "IO_5_6") (pintype "bidirectional"))
      (node (ref "U$4") (pin "6") (pinfunction "IO_5_6") (pintype "bidirectional"))
      (node (ref "Z80") (pin "8") (pinfunction "D3_8") (pintype "bidirectional"))
    )
    (net (code "38") (name "/D4") (class "Default")
      (node (ref "EXPANSION1") (pin "14") (pinfunction "I/O5_14") (pintype "bidirectional"))
      (node (ref "EXPANSION2") (pin "11") (pinfunction "11_11") (pintype "passive"))
      (node (ref "RAM_HM6116") (pin "14") (pinfunction "O4_14") (pintype "tri_state"))
      (node (ref "ROM_AT28C16") (pin "14") (pinfunction "I/O5_14") (pintype "bidirectional"))
      (node (ref "U$2") (pin "7") (pinfunction "D4_7") (pintype "bidirectional"))
      (node (ref "U$3") (pin "8") (pinfunction "IO_6_8") (pintype "bidirectional"))
      (node (ref "U$4") (pin "8") (pinfunction "IO_6_8") (pintype "bidirectional"))
      (node (ref "Z80") (pin "7") (pinfunction "D4_7") (pintype "bidirectional"))
    )
    (net (code "39") (name "/D5") (class "Default")
      (node (ref "EXPANSION1") (pin "15") (pinfunction "I/O6_15") (pintype "bidirectional"))
      (node (ref "EXPANSION2") (pin "13") (pinfunction "13_13") (pintype "passive"))
      (node (ref "RAM_HM6116") (pin "15") (pinfunction "O5_15") (pintype "tri_state"))
      (node (ref "ROM_AT28C16") (pin "15") (pinfunction "I/O6_15") (pintype "bidirectional"))
      (node (ref "U$2") (pin "6") (pinfunction "D5_6") (pintype "bidirectional"))
      (node (ref "U$3") (pin "10") (pinfunction "IO_7_10") (pintype "bidirectional"))
      (node (ref "U$4") (pin "10") (pinfunction "IO_7_10") (pintype "bidirectional"))
      (node (ref "Z80") (pin "9") (pinfunction "D5_9") (pintype "bidirectional"))
    )
    (net (code "40") (name "/D6") (class "Default")
      (node (ref "EXPANSION1") (pin "16") (pinfunction "I/O7_16") (pintype "bidirectional"))
      (node (ref "EXPANSION2") (pin "15") (pinfunction "15_15") (pintype "passive"))
      (node (ref "RAM_HM6116") (pin "16") (pinfunction "O6_16") (pintype "tri_state"))
      (node (ref "ROM_AT28C16") (pin "16") (pinfunction "I/O7_16") (pintype "bidirectional"))
      (node (ref "U$2") (pin "5") (pinfunction "D6_5") (pintype "bidirectional"))
      (node (ref "U$3") (pin "12") (pinfunction "IO_8_12") (pintype "bidirectional"))
      (node (ref "U$4") (pin "12") (pinfunction "IO_8_12") (pintype "bidirectional"))
      (node (ref "Z80") (pin "10") (pinfunction "D6_10") (pintype "bidirectional"))
    )
    (net (code "41") (name "/D7") (class "Default")
      (node (ref "EXPANSION1") (pin "17") (pinfunction "I/O8_17") (pintype "bidirectional"))
      (node (ref "EXPANSION2") (pin "17") (pinfunction "17_17") (pintype "passive"))
      (node (ref "RAM_HM6116") (pin "17") (pinfunction "O7_17") (pintype "tri_state"))
      (node (ref "ROM_AT28C16") (pin "17") (pinfunction "I/O8_17") (pintype "bidirectional"))
      (node (ref "U$2") (pin "4") (pinfunction "D7_4") (pintype "bidirectional"))
      (node (ref "U$3") (pin "13") (pinfunction "IO_9_13") (pintype "bidirectional"))
      (node (ref "U$4") (pin "13") (pinfunction "IO_9_13") (pintype "bidirectional"))
      (node (ref "Z80") (pin "13") (pinfunction "D7_13") (pintype "bidirectional"))
    )
    (net (code "42") (name "/DP") (class "Default")
      (node (ref "DIS1") (pin "5") (pinfunction "DP_5") (pintype "passive"))
      (node (ref "DIS2") (pin "5") (pinfunction "DP_5") (pintype "passive"))
      (node (ref "DIS3") (pin "5") (pinfunction "DP_5") (pintype "passive"))
      (node (ref "DIS4") (pin "5") (pinfunction "DP_5") (pintype "passive"))
      (node (ref "DIS5") (pin "5") (pinfunction "DP_5") (pintype "passive"))
      (node (ref "DIS6") (pin "5") (pinfunction "DP_5") (pintype "passive"))
      (node (ref "R2") (pin "2") (pinfunction "2_2") (pintype "passive"))
    )
    (net (code "43") (name "/E") (class "Default")
      (node (ref "DIS1") (pin "1") (pinfunction "E_1") (pintype "passive"))
      (node (ref "DIS2") (pin "1") (pinfunction "E_1") (pintype "passive"))
      (node (ref "DIS3") (pin "1") (pinfunction "E_1") (pintype "passive"))
      (node (ref "DIS4") (pin "1") (pinfunction "E_1") (pintype "passive"))
      (node (ref "DIS5") (pin "1") (pinfunction "E_1") (pintype "passive"))
      (node (ref "DIS6") (pin "1") (pinfunction "E_1") (pintype "passive"))
      (node (ref "R6") (pin "2") (pinfunction "2_2") (pintype "passive"))
    )
    (net (code "44") (name "/EXP1~{CS}") (class "Default")
      (node (ref "EXPANSION1") (pin "18") (pinfunction "~{CS}_18") (pintype "input"))
      (node (ref "EXPANSION2") (pin "23") (pinfunction "23_23") (pintype "passive"))
      (node (ref "U$1") (pin "20") (pinfunction "IO_14_20") (pintype "bidirectional"))
    )
    (net (code "45") (name "/F") (class "Default")
      (node (ref "DIS1") (pin "9") (pinfunction "F_9") (pintype "passive"))
      (node (ref "DIS2") (pin "9") (pinfunction "F_9") (pintype "passive"))
      (node (ref "DIS3") (pin "9") (pinfunction "F_9") (pintype "passive"))
      (node (ref "DIS4") (pin "9") (pinfunction "F_9") (pintype "passive"))
      (node (ref "DIS5") (pin "9") (pinfunction "F_9") (pintype "passive"))
      (node (ref "DIS6") (pin "9") (pinfunction "F_9") (pintype "passive"))
      (node (ref "R4") (pin "2") (pinfunction "2_2") (pintype "passive"))
    )
    (net (code "46") (name "/G") (class "Default")
      (node (ref "DIS1") (pin "10") (pinfunction "G_10") (pintype "passive"))
      (node (ref "DIS2") (pin "10") (pinfunction "G_10") (pintype "passive"))
      (node (ref "DIS3") (pin "10") (pinfunction "G_10") (pintype "passive"))
      (node (ref "DIS4") (pin "10") (pinfunction "G_10") (pintype "passive"))
      (node (ref "DIS5") (pin "10") (pinfunction "G_10") (pintype "passive"))
      (node (ref "DIS6") (pin "10") (pinfunction "G_10") (pintype "passive"))
      (node (ref "R3") (pin "2") (pinfunction "2_2") (pintype "passive"))
    )
    (net (code "47") (name "/GND") (class "Default")
      (node (ref "C1") (pin "-") (pinfunction "-_-") (pintype "passive"))
      (node (ref "C10") (pin "+") (pinfunction "+_+") (pintype "passive"))
      (node (ref "C2") (pin "1") (pinfunction "1_1") (pintype "passive"))
      (node (ref "C3") (pin "1") (pinfunction "1_1") (pintype "passive"))
      (node (ref "C4") (pin "1") (pinfunction "1_1") (pintype "passive"))
      (node (ref "C5") (pin "1") (pinfunction "1_1") (pintype "passive"))
      (node (ref "C6") (pin "1") (pinfunction "1_1") (pintype "passive"))
      (node (ref "C7") (pin "2") (pinfunction "2_2") (pintype "passive"))
      (node (ref "C8") (pin "2") (pinfunction "2_2") (pintype "passive"))
      (node (ref "C9") (pin "2") (pinfunction "2_2") (pintype "passive"))
      (node (ref "DISABLE_CLK") (pin "1") (pinfunction "1_1") (pintype "passive"))
      (node (ref "EXPANSION2") (pin "2") (pinfunction "2_2") (pintype "passive"))
      (node (ref "IC5") (pin "1") (pinfunction "ADJ_1") (pintype "input"))
      (node (ref "JTAG1") (pin "4") (pinfunction "4_4") (pintype "passive"))
      (node (ref "JTAG2") (pin "4") (pinfunction "4_4") (pintype "passive"))
      (node (ref "JTAG3") (pin "4") (pinfunction "4_4") (pintype "passive"))
      (node (ref "RESET") (pin "4") (pinfunction "P1_4") (pintype "passive"))
      (node (ref "SHIFT") (pin "4") (pinfunction "P1_4") (pintype "passive"))
      (node (ref "U$1") (pin "11") (pinfunction "GND_2_11") (pintype "passive"))
      (node (ref "U$1") (pin "16") (pinfunction "GND_3_16") (pintype "passive"))
      (node (ref "U$1") (pin "24") (pinfunction "GND_5_24") (pintype "passive"))
      (node (ref "U$1") (pin "30") (pinfunction "GND_6_30") (pintype "passive"))
      (node (ref "U$1") (pin "36") (pinfunction "GND_36") (pintype "passive"))
      (node (ref "U$1") (pin "4") (pinfunction "GND_4_4") (pintype "passive"))
      (node (ref "U$2") (pin "1") (pinfunction "GND_1") (pintype "power_in"))
      (node (ref "U$2") (pin "28") (pinfunction "~{CS}_28") (pintype "input"))
      (node (ref "U$3") (pin "11") (pinfunction "GND_2_11") (pintype "passive"))
      (node (ref "U$3") (pin "16") (pinfunction "GND_3_16") (pintype "passive"))
      (node (ref "U$3") (pin "24") (pinfunction "GND_5_24") (pintype "passive"))
      (node (ref "U$3") (pin "30") (pinfunction "GND_6_30") (pintype "passive"))
      (node (ref "U$3") (pin "36") (pinfunction "GND_36") (pintype "passive"))
      (node (ref "U$3") (pin "4") (pinfunction "GND_4_4") (pintype "passive"))
      (node (ref "U$4") (pin "11") (pinfunction "GND_2_11") (pintype "passive"))
      (node (ref "U$4") (pin "16") (pinfunction "GND_3_16") (pintype "passive"))
      (node (ref "U$4") (pin "24") (pinfunction "GND_5_24") (pintype "passive"))
      (node (ref "U$4") (pin "30") (pinfunction "GND_6_30") (pintype "passive"))
      (node (ref "U$4") (pin "36") (pinfunction "GND_36") (pintype "passive"))
      (node (ref "U$4") (pin "4") (pinfunction "GND_4_4") (pintype "passive"))
      (node (ref "U$5") (pin "2") (pinfunction "GND_2") (pintype "power_in"))
      (node (ref "U$6") (pin "GND") (pinfunction "GND_GND") (pintype "bidirectional"))
      (node (ref "Z80") (pin "29") (pinfunction "GND_29") (pintype "power_in"))
    )
    (net (code "48") (name "/HALT") (class "Default")
      (node (ref "Z80") (pin "18") (pinfunction "HALT_18") (pintype "output"))
    )
    (net (code "49") (name "/IORQ") (class "Default")
      (node (ref "EXPANSION2") (pin "33") (pinfunction "33_33") (pintype "passive"))
      (node (ref "U$1") (pin "40") (pinfunction "INPUT/OE2/GCLK2_40") (pintype "input"))
      (node (ref "Z80") (pin "20") (pinfunction "IORQ_20") (pintype "output"))
    )
    (net (code "50") (name "/M1") (class "Default")
      (node (ref "Z80") (pin "27") (pinfunction "M1_27") (pintype "output"))
    )
    (net (code "51") (name "/MREQ") (class "Default")
      (node (ref "EXPANSION2") (pin "35") (pinfunction "35_35") (pintype "passive"))
      (node (ref "U$1") (pin "38") (pinfunction "INPUT/OE1_38") (pintype "input"))
      (node (ref "Z80") (pin "19") (pinfunction "MREQ_19") (pintype "output"))
    )
    (net (code "52") (name "/NMI") (class "Default")
      (node (ref "EXPANSION2") (pin "38") (pinfunction "38_38") (pintype "passive"))
      (node (ref "U$3") (pin "14") (pinfunction "IO_10_14") (pintype "bidirectional"))
      (node (ref "Z80") (pin "17") (pinfunction "NMI_17") (pintype "input"))
    )
    (net (code "53") (name "/PORT3") (class "Default")
      (node (ref "EXPANSION2") (pin "29") (pinfunction "29_29") (pintype "passive"))
      (node (ref "PORT3") (pin "1") (pinfunction "P_1") (pintype "passive"))
      (node (ref "U$1") (pin "27") (pinfunction "IO_19_27") (pintype "bidirectional"))
    )
    (net (code "54") (name "/PORT4") (class "Default")
      (node (ref "EXPANSION2") (pin "27") (pinfunction "27_27") (pintype "passive"))
      (node (ref "PORT4") (pin "1") (pinfunction "P_1") (pintype "passive"))
      (node (ref "U$1") (pin "25") (pinfunction "IO_18_25") (pintype "bidirectional"))
    )
    (net (code "55") (name "/PORT5") (class "Default")
      (node (ref "EXPANSION2") (pin "25") (pinfunction "25_25") (pintype "passive"))
      (node (ref "PORT5") (pin "1") (pinfunction "P_1") (pintype "passive"))
      (node (ref "U$1") (pin "23") (pinfunction "IO_17_23") (pintype "bidirectional"))
    )
    (net (code "56") (name "/PORT6") (class "Default")
      (node (ref "PORT6") (pin "1") (pinfunction "P_1") (pintype "passive"))
      (node (ref "U$1") (pin "22") (pinfunction "IO_16_22") (pintype "bidirectional"))
    )
    (net (code "57") (name "/PORT_COLUMN") (class "Default")
      (node (ref "U$1") (pin "31") (pinfunction "IO_21_31") (pintype "bidirectional"))
      (node (ref "U$4") (pin "18") (pinfunction "IO_12_18") (pintype "bidirectional"))
    )
    (net (code "58") (name "/PORT_KB") (class "Default")
      (node (ref "U$1") (pin "33") (pinfunction "IO_22_33") (pintype "bidirectional"))
      (node (ref "U$3") (pin "38") (pinfunction "INPUT/OE1_38") (pintype "input"))
    )
    (net (code "59") (name "/PORT_ROW") (class "Default")
      (node (ref "U$1") (pin "28") (pinfunction "IO_20_28") (pintype "bidirectional"))
      (node (ref "U$4") (pin "19") (pinfunction "IO_13_19") (pintype "bidirectional"))
    )
    (net (code "60") (name "/RAM~{CS}") (class "Default")
      (node (ref "RAM_HM6116") (pin "18") (pinfunction "~{CE}_18") (pintype "input"))
      (node (ref "U$1") (pin "18") (pinfunction "IO_12_18") (pintype "bidirectional"))
    )
    (net (code "61") (name "/RFSH") (class "Default")
      (node (ref "Z80") (pin "28") (pinfunction "RFSH_28") (pintype "output"))
    )
    (net (code "62") (name "/ROM~{CS}") (class "Default")
      (node (ref "ROM_AT28C16") (pin "18") (pinfunction "~{CS}_18") (pintype "input"))
      (node (ref "U$1") (pin "19") (pinfunction "IO_13_19") (pintype "bidirectional"))
    )
    (net (code "63") (name "/SEG0") (class "Default")
      (node (ref "DIS1") (pin "3") (pinfunction "CC_3") (pintype "passive"))
      (node (ref "DIS1") (pin "8") (pinfunction "CC_8") (pintype "passive"))
      (node (ref "U$4") (pin "27") (pinfunction "IO_19_27") (pintype "bidirectional"))
    )
    (net (code "64") (name "/SEG1") (class "Default")
      (node (ref "DIS2") (pin "3") (pinfunction "CC_3") (pintype "passive"))
      (node (ref "DIS2") (pin "8") (pinfunction "CC_8") (pintype "passive"))
      (node (ref "U$4") (pin "25") (pinfunction "IO_18_25") (pintype "bidirectional"))
    )
    (net (code "65") (name "/SEG2") (class "Default")
      (node (ref "DIS3") (pin "3") (pinfunction "CC_3") (pintype "passive"))
      (node (ref "DIS3") (pin "8") (pinfunction "CC_8") (pintype "passive"))
      (node (ref "U$4") (pin "23") (pinfunction "IO_17_23") (pintype "bidirectional"))
    )
    (net (code "66") (name "/SEG3") (class "Default")
      (node (ref "DIS4") (pin "3") (pinfunction "CC_3") (pintype "passive"))
      (node (ref "DIS4") (pin "8") (pinfunction "CC_8") (pintype "passive"))
      (node (ref "U$4") (pin "22") (pinfunction "IO_16_22") (pintype "bidirectional"))
    )
    (net (code "67") (name "/SEG4") (class "Default")
      (node (ref "DIS5") (pin "3") (pinfunction "CC_3") (pintype "passive"))
      (node (ref "DIS5") (pin "8") (pinfunction "CC_8") (pintype "passive"))
      (node (ref "U$4") (pin "21") (pinfunction "IO_15_21") (pintype "bidirectional"))
    )
    (net (code "68") (name "/SEG5") (class "Default")
      (node (ref "DIS6") (pin "3") (pinfunction "CC_3") (pintype "passive"))
      (node (ref "DIS6") (pin "8") (pinfunction "CC_8") (pintype "passive"))
      (node (ref "U$4") (pin "20") (pinfunction "IO_14_20") (pintype "bidirectional"))
    )
    (net (code "69") (name "/SHIFT") (class "Default")
      (node (ref "R1") (pin "1") (pinfunction "1_1") (pintype "passive"))
      (node (ref "SHIFT") (pin "2") (pinfunction "S1_2") (pintype "passive"))
      (node (ref "U$3") (pin "25") (pinfunction "IO_18_25") (pintype "bidirectional"))
    )
    (net (code "70") (name "/SND") (class "Default")
      (node (ref "U$2") (pin "2") (pinfunction "SND_2") (pintype "bidirectional"))
    )
    (net (code "71") (name "/TCK") (class "Default")
      (node (ref "JTAG1") (pin "5") (pinfunction "5_5") (pintype "passive"))
      (node (ref "U$4") (pin "26") (pinfunction "IO/TCK_26") (pintype "bidirectional"))
    )
    (net (code "72") (name "/TDI") (class "Default")
      (node (ref "JTAG1") (pin "6") (pinfunction "6_6") (pintype "passive"))
      (node (ref "U$4") (pin "1") (pinfunction "IO/TDI_1") (pintype "bidirectional"))
    )
    (net (code "73") (name "/TDO") (class "Default")
      (node (ref "JTAG1") (pin "1") (pinfunction "1_1") (pintype "passive"))
      (node (ref "U$4") (pin "32") (pinfunction "IO/TDO_32") (pintype "bidirectional"))
    )
    (net (code "74") (name "/TMS") (class "Default")
      (node (ref "JTAG1") (pin "3") (pinfunction "3_3") (pintype "passive"))
      (node (ref "U$4") (pin "7") (pinfunction "IO/TMS_7") (pintype "bidirectional"))
    )
    (net (code "75") (name "/VCC") (class "Default")
      (node (ref "C10") (pin "-") (pinfunction "-_-") (pintype "passive"))
      (node (ref "C2") (pin "2") (pinfunction "2_2") (pintype "passive"))
      (node (ref "C3") (pin "2") (pinfunction "2_2") (pintype "passive"))
      (node (ref "C4") (pin "2") (pinfunction "2_2") (pintype "passive"))
      (node (ref "C5") (pin "2") (pinfunction "2_2") (pintype "passive"))
      (node (ref "C6") (pin "2") (pinfunction "2_2") (pintype "passive"))
      (node (ref "EXPANSION2") (pin "1") (pinfunction "1_1") (pintype "passive"))
      (node (ref "IC5") (pin "3") (pinfunction "IN_3") (pintype "input"))
      (node (ref "R1") (pin "2") (pinfunction "2_2") (pintype "passive"))
      (node (ref "R10") (pin "1") (pinfunction "1_1") (pintype "passive"))
      (node (ref "R11") (pin "1") (pinfunction "1_1") (pintype "passive"))
      (node (ref "R12") (pin "2") (pinfunction "2_2") (pintype "passive"))
      (node (ref "R13") (pin "1") (pinfunction "1_1") (pintype "passive"))
      (node (ref "R14") (pin "1") (pinfunction "1_1") (pintype "passive"))
      (node (ref "R15") (pin "1") (pinfunction "1_1") (pintype "passive"))
      (node (ref "R16") (pin "1") (pinfunction "1_1") (pintype "passive"))
      (node (ref "R17") (pin "1") (pinfunction "1_1") (pintype "passive"))
      (node (ref "R18") (pin "1") (pinfunction "1_1") (pintype "passive"))
      (node (ref "R19") (pin "1") (pinfunction "1_1") (pintype "passive"))
      (node (ref "U$2") (pin "32") (pinfunction "VCC_32") (pintype "power_in"))
      (node (ref "U$6") (pin "VBUS") (pinfunction "VBUS_VBUS") (pintype "bidirectional"))
      (node (ref "Z80") (pin "11") (pinfunction "VCC_11") (pintype "power_in"))
    )
    (net (code "76") (name "/WAIT") (class "Default")
      (node (ref "R10") (pin "2") (pinfunction "2_2") (pintype "passive"))
      (node (ref "Z80") (pin "24") (pinfunction "WAIT_24") (pintype "input"))
    )
    (net (code "77") (name "/X1") (class "Default")
      (node (ref "+") (pin "3") (pinfunction "P_3") (pintype "passive"))
      (node (ref "0") (pin "3") (pinfunction "P_3") (pintype "passive"))
      (node (ref "4") (pin "3") (pinfunction "P_3") (pintype "passive"))
      (node (ref "8") (pin "3") (pinfunction "P_3") (pintype "passive"))
      (node (ref "C") (pin "3") (pinfunction "P_3") (pintype "passive"))
      (node (ref "ROW") (pin "1") (pinfunction "1_1") (pintype "passive"))
      (node (ref "U$3") (pin "44") (pinfunction "IO_44") (pintype "bidirectional"))
    )
    (net (code "78") (name "/X2") (class "Default")
      (node (ref "-") (pin "3") (pinfunction "P_3") (pintype "passive"))
      (node (ref "1") (pin "3") (pinfunction "P_3") (pintype "passive"))
      (node (ref "5") (pin "3") (pinfunction "P_3") (pintype "passive"))
      (node (ref "9") (pin "3") (pinfunction "P_3") (pintype "passive"))
      (node (ref "D") (pin "3") (pinfunction "P_3") (pintype "passive"))
      (node (ref "ROW") (pin "2") (pinfunction "2_2") (pintype "passive"))
      (node (ref "U$3") (pin "43") (pinfunction "IO_26_43") (pintype "bidirectional"))
    )
    (net (code "79") (name "/X3") (class "Default")
      (node (ref "2") (pin "3") (pinfunction "P_3") (pintype "passive"))
      (node (ref "6") (pin "3") (pinfunction "P_3") (pintype "passive"))
      (node (ref "A") (pin "3") (pinfunction "P_3") (pintype "passive"))
      (node (ref "E") (pin "3") (pinfunction "P_3") (pintype "passive"))
      (node (ref "GO") (pin "3") (pinfunction "P_3") (pintype "passive"))
      (node (ref "ROW") (pin "3") (pinfunction "3_3") (pintype "passive"))
      (node (ref "U$3") (pin "42") (pinfunction "IO_25_42") (pintype "bidirectional"))
    )
    (net (code "80") (name "/X4") (class "Default")
      (node (ref "3") (pin "3") (pinfunction "P_3") (pintype "passive"))
      (node (ref "7") (pin "3") (pinfunction "P_3") (pintype "passive"))
      (node (ref "AD") (pin "3") (pinfunction "P_3") (pintype "passive"))
      (node (ref "B") (pin "3") (pinfunction "P_3") (pintype "passive"))
      (node (ref "F") (pin "3") (pinfunction "P_3") (pintype "passive"))
      (node (ref "ROW") (pin "4") (pinfunction "4_4") (pintype "passive"))
      (node (ref "U$3") (pin "35") (pinfunction "IO_24_35") (pintype "bidirectional"))
    )
    (net (code "81") (name "/X5") (class "Default")
      (node (ref "ROW") (pin "5") (pinfunction "5_5") (pintype "passive"))
      (node (ref "U$3") (pin "23") (pinfunction "IO_17_23") (pintype "bidirectional"))
    )
    (net (code "82") (name "/X6") (class "Default")
      (node (ref "ROW") (pin "6") (pinfunction "6_6") (pintype "passive"))
      (node (ref "U$3") (pin "22") (pinfunction "IO_16_22") (pintype "bidirectional"))
    )
    (net (code "83") (name "/X7") (class "Default")
      (node (ref "ROW") (pin "7") (pinfunction "7_7") (pintype "passive"))
      (node (ref "U$3") (pin "21") (pinfunction "IO_15_21") (pintype "bidirectional"))
    )
    (net (code "84") (name "/X8") (class "Default")
      (node (ref "ROW") (pin "8") (pinfunction "8_8") (pintype "passive"))
      (node (ref "U$3") (pin "18") (pinfunction "IO_12_18") (pintype "bidirectional"))
    )
    (net (code "85") (name "/Y1") (class "Default")
      (node (ref "0") (pin "2") (pinfunction "S1_2") (pintype "passive"))
      (node (ref "1") (pin "2") (pinfunction "S1_2") (pintype "passive"))
      (node (ref "2") (pin "2") (pinfunction "S1_2") (pintype "passive"))
      (node (ref "3") (pin "2") (pinfunction "S1_2") (pintype "passive"))
      (node (ref "COLUMN") (pin "1") (pinfunction "1_1") (pintype "passive"))
      (node (ref "R18") (pin "2") (pinfunction "2_2") (pintype "passive"))
      (node (ref "U$3") (pin "34") (pinfunction "IO_23_34") (pintype "bidirectional"))
    )
    (net (code "86") (name "/Y2") (class "Default")
      (node (ref "4") (pin "2") (pinfunction "S1_2") (pintype "passive"))
      (node (ref "5") (pin "2") (pinfunction "S1_2") (pintype "passive"))
      (node (ref "6") (pin "2") (pinfunction "S1_2") (pintype "passive"))
      (node (ref "7") (pin "2") (pinfunction "S1_2") (pintype "passive"))
      (node (ref "COLUMN") (pin "2") (pinfunction "2_2") (pintype "passive"))
      (node (ref "R17") (pin "2") (pinfunction "2_2") (pintype "passive"))
      (node (ref "U$3") (pin "33") (pinfunction "IO_22_33") (pintype "bidirectional"))
    )
    (net (code "87") (name "/Y3") (class "Default")
      (node (ref "8") (pin "2") (pinfunction "S1_2") (pintype "passive"))
      (node (ref "9") (pin "2") (pinfunction "S1_2") (pintype "passive"))
      (node (ref "A") (pin "2") (pinfunction "S1_2") (pintype "passive"))
      (node (ref "B") (pin "2") (pinfunction "S1_2") (pintype "passive"))
      (node (ref "COLUMN") (pin "3") (pinfunction "3_3") (pintype "passive"))
      (node (ref "R16") (pin "2") (pinfunction "2_2") (pintype "passive"))
      (node (ref "U$3") (pin "31") (pinfunction "IO_21_31") (pintype "bidirectional"))
    )
    (net (code "88") (name "/Y4") (class "Default")
      (node (ref "C") (pin "2") (pinfunction "S1_2") (pintype "passive"))
      (node (ref "COLUMN") (pin "4") (pinfunction "4_4") (pintype "passive"))
      (node (ref "D") (pin "2") (pinfunction "S1_2") (pintype "passive"))
      (node (ref "E") (pin "2") (pinfunction "S1_2") (pintype "passive"))
      (node (ref "F") (pin "2") (pinfunction "S1_2") (pintype "passive"))
      (node (ref "R15") (pin "2") (pinfunction "2_2") (pintype "passive"))
      (node (ref "U$3") (pin "28") (pinfunction "IO_20_28") (pintype "bidirectional"))
    )
    (net (code "89") (name "/Y5") (class "Default")
      (node (ref "+") (pin "2") (pinfunction "S1_2") (pintype "passive"))
      (node (ref "-") (pin "2") (pinfunction "S1_2") (pintype "passive"))
      (node (ref "AD") (pin "2") (pinfunction "S1_2") (pintype "passive"))
      (node (ref "COLUMN") (pin "5") (pinfunction "5_5") (pintype "passive"))
      (node (ref "GO") (pin "2") (pinfunction "S1_2") (pintype "passive"))
      (node (ref "R19") (pin "2") (pinfunction "2_2") (pintype "passive"))
      (node (ref "U$3") (pin "27") (pinfunction "IO_19_27") (pintype "bidirectional"))
    )
    (net (code "90") (name "/Y6") (class "Default")
      (node (ref "COLUMN") (pin "6") (pinfunction "6_6") (pintype "passive"))
      (node (ref "U$3") (pin "20") (pinfunction "IO_14_20") (pintype "bidirectional"))
    )
    (net (code "91") (name "/Y7") (class "Default")
      (node (ref "COLUMN") (pin "7") (pinfunction "7_7") (pintype "passive"))
      (node (ref "U$3") (pin "19") (pinfunction "IO_13_19") (pintype "bidirectional"))
    )
    (net (code "92") (name "/Y8") (class "Default")
      (node (ref "COLUMN") (pin "8") (pinfunction "8_8") (pintype "passive"))
      (node (ref "U$3") (pin "15") (pinfunction "IO_11_15") (pintype "bidirectional"))
    )
    (net (code "94") (name "/~{INT}") (class "Default")
      (node (ref "EXPANSION2") (pin "40") (pinfunction "40_40") (pintype "passive"))
      (node (ref "R13") (pin "2") (pinfunction "2_2") (pintype "passive"))
      (node (ref "Z80") (pin "16") (pinfunction "INT_16") (pintype "input"))
    )
    (net (code "95") (name "/~{RD}") (class "Default")
      (node (ref "EXPANSION1") (pin "20") (pinfunction "~{OE}_20") (pintype "input"))
      (node (ref "EXPANSION2") (pin "37") (pinfunction "37_37") (pintype "passive"))
      (node (ref "RAM_HM6116") (pin "20") (pinfunction "~{OE}_20") (pintype "input"))
      (node (ref "ROM_AT28C16") (pin "20") (pinfunction "~{OE}_20") (pintype "input"))
      (node (ref "U$1") (pin "3") (pinfunction "IO_3_3") (pintype "bidirectional"))
      (node (ref "U$3") (pin "40") (pinfunction "INPUT/OE2/GCLK2_40") (pintype "input"))
      (node (ref "U$4") (pin "38") (pinfunction "INPUT/OE1_38") (pintype "input"))
      (node (ref "Z80") (pin "21") (pinfunction "RD_21") (pintype "output"))
    )
    (net (code "96") (name "/~{RESET}") (class "Default")
      (node (ref "C1") (pin "+") (pinfunction "+_+") (pintype "passive"))
      (node (ref "EXPANSION2") (pin "31") (pinfunction "31_31") (pintype "passive"))
      (node (ref "R11") (pin "2") (pinfunction "2_2") (pintype "passive"))
      (node (ref "R12") (pin "1") (pinfunction "1_1") (pintype "passive"))
      (node (ref "RESET") (pin "2") (pinfunction "S1_2") (pintype "passive"))
      (node (ref "U$1") (pin "39") (pinfunction "INPUT/GCLR_39") (pintype "input"))
      (node (ref "U$2") (pin "3") (pinfunction "~{RST}_3") (pintype "bidirectional"))
      (node (ref "Z80") (pin "26") (pinfunction "RESET_26") (pintype "input"))
    )
    (net (code "97") (name "/~{WR}") (class "Default")
      (node (ref "EXPANSION1") (pin "21") (pinfunction "~{WE}_21") (pintype "input"))
      (node (ref "EXPANSION2") (pin "39") (pinfunction "39_39") (pintype "passive"))
      (node (ref "RAM_HM6116") (pin "21") (pinfunction "VPP_21") (pintype "input"))
      (node (ref "ROM_AT28C16") (pin "21") (pinfunction "~{WE}_21") (pintype "input"))
      (node (ref "U$1") (pin "2") (pinfunction "IO_2_2") (pintype "bidirectional"))
      (node (ref "U$3") (pin "39") (pinfunction "INPUT/GCLR_39") (pintype "input"))
      (node (ref "U$4") (pin "39") (pinfunction "INPUT/GCLR_39") (pintype "input"))
      (node (ref "Z80") (pin "22") (pinfunction "WR_22") (pintype "output"))
    )
    (net (code "98") (name "Net-(U$1-IO{slash}TCK)") (class "Default")
      (node (ref "JTAG2") (pin "5") (pinfunction "5_5") (pintype "passive"))
      (node (ref "U$1") (pin "26") (pinfunction "IO/TCK_26") (pintype "bidirectional"))
    )
    (net (code "99") (name "Net-(U$1-IO{slash}TDI)") (class "Default")
      (node (ref "JTAG2") (pin "6") (pinfunction "6_6") (pintype "passive"))
      (node (ref "U$1") (pin "1") (pinfunction "IO/TDI_1") (pintype "bidirectional"))
    )
    (net (code "100") (name "Net-(U$1-IO{slash}TDO)") (class "Default")
      (node (ref "JTAG2") (pin "1") (pinfunction "1_1") (pintype "passive"))
      (node (ref "U$1") (pin "32") (pinfunction "IO/TDO_32") (pintype "bidirectional"))
    )
    (net (code "101") (name "Net-(U$1-IO{slash}TMS)") (class "Default")
      (node (ref "JTAG2") (pin "3") (pinfunction "3_3") (pintype "passive"))
      (node (ref "U$1") (pin "7") (pinfunction "IO/TMS_7") (pintype "bidirectional"))
    )
    (net (code "102") (name "Net-(U$3-IO{slash}TCK)") (class "Default")
      (node (ref "JTAG3") (pin "5") (pinfunction "5_5") (pintype "passive"))
      (node (ref "U$3") (pin "26") (pinfunction "IO/TCK_26") (pintype "bidirectional"))
    )
    (net (code "103") (name "Net-(U$3-IO{slash}TDI)") (class "Default")
      (node (ref "JTAG3") (pin "6") (pinfunction "6_6") (pintype "passive"))
      (node (ref "U$3") (pin "1") (pinfunction "IO/TDI_1") (pintype "bidirectional"))
    )
    (net (code "104") (name "Net-(U$3-IO{slash}TDO)") (class "Default")
      (node (ref "JTAG3") (pin "1") (pinfunction "1_1") (pintype "passive"))
      (node (ref "U$3") (pin "32") (pinfunction "IO/TDO_32") (pintype "bidirectional"))
    )
    (net (code "105") (name "Net-(U$3-IO{slash}TMS)") (class "Default")
      (node (ref "JTAG3") (pin "3") (pinfunction "3_3") (pintype "passive"))
      (node (ref "U$3") (pin "7") (pinfunction "IO/TMS_7") (pintype "bidirectional"))
    )
    (net (code "106") (name "Net-(U$4-IO)") (class "Default")
      (node (ref "R9") (pin "1") (pinfunction "1_1") (pintype "passive"))
      (node (ref "U$4") (pin "44") (pinfunction "IO_44") (pintype "bidirectional"))
    )
    (net (code "107") (name "Net-(U$4-IO_20)") (class "Default")
      (node (ref "R2") (pin "1") (pinfunction "1_1") (pintype "passive"))
      (node (ref "U$4") (pin "28") (pinfunction "IO_20_28") (pintype "bidirectional"))
    )
    (net (code "108") (name "Net-(U$4-IO_21)") (class "Default")
      (node (ref "R3") (pin "1") (pinfunction "1_1") (pintype "passive"))
      (node (ref "U$4") (pin "31") (pinfunction "IO_21_31") (pintype "bidirectional"))
    )
    (net (code "109") (name "Net-(U$4-IO_22)") (class "Default")
      (node (ref "R4") (pin "1") (pinfunction "1_1") (pintype "passive"))
      (node (ref "U$4") (pin "33") (pinfunction "IO_22_33") (pintype "bidirectional"))
    )
    (net (code "110") (name "Net-(U$4-IO_23)") (class "Default")
      (node (ref "R6") (pin "1") (pinfunction "1_1") (pintype "passive"))
      (node (ref "U$4") (pin "34") (pinfunction "IO_23_34") (pintype "bidirectional"))
    )
    (net (code "111") (name "Net-(U$4-IO_24)") (class "Default")
      (node (ref "R5") (pin "1") (pinfunction "1_1") (pintype "passive"))
      (node (ref "U$4") (pin "35") (pinfunction "IO_24_35") (pintype "bidirectional"))
    )
    (net (code "112") (name "Net-(U$4-IO_25)") (class "Default")
      (node (ref "R7") (pin "1") (pinfunction "1_1") (pintype "passive"))
      (node (ref "U$4") (pin "42") (pinfunction "IO_25_42") (pintype "bidirectional"))
    )
    (net (code "113") (name "Net-(U$4-IO_26)") (class "Default")
      (node (ref "R8") (pin "1") (pinfunction "1_1") (pintype "passive"))
      (node (ref "U$4") (pin "43") (pinfunction "IO_26_43") (pintype "bidirectional"))
    )
    (net (code "114") (name "Net-(U$5-TRI)") (class "Default")
      (node (ref "DISABLE_CLK") (pin "2") (pinfunction "2_2") (pintype "passive"))
      (node (ref "U$5") (pin "1") (pinfunction "TRI_1") (pintype "input"))
    )
    (net (code "115") (name "unconnected-(+-P1-Pad4)") (class "Default")
      (node (ref "+") (pin "4") (pinfunction "P1_4") (pintype "passive"))
    )
    (net (code "116") (name "unconnected-(+-S-Pad1)") (class "Default")
      (node (ref "+") (pin "1") (pinfunction "S_1") (pintype "passive"))
    )
    (net (code "117") (name "unconnected-(--P1-Pad4)") (class "Default")
      (node (ref "-") (pin "4") (pinfunction "P1_4") (pintype "passive"))
    )
    (net (code "118") (name "unconnected-(--S-Pad1)") (class "Default")
      (node (ref "-") (pin "1") (pinfunction "S_1") (pintype "passive"))
    )
    (net (code "119") (name "unconnected-(0-P1-Pad4)") (class "Default")
      (node (ref "0") (pin "4") (pinfunction "P1_4") (pintype "passive"))
    )
    (net (code "120") (name "unconnected-(0-S-Pad1)") (class "Default")
      (node (ref "0") (pin "1") (pinfunction "S_1") (pintype "passive"))
    )
    (net (code "121") (name "unconnected-(1-P1-Pad4)") (class "Default")
      (node (ref "1") (pin "4") (pinfunction "P1_4") (pintype "passive"))
    )
    (net (code "122") (name "unconnected-(1-S-Pad1)") (class "Default")
      (node (ref "1") (pin "1") (pinfunction "S_1") (pintype "passive"))
    )
    (net (code "123") (name "unconnected-(2-P1-Pad4)") (class "Default")
      (node (ref "2") (pin "4") (pinfunction "P1_4") (pintype "passive"))
    )
    (net (code "124") (name "unconnected-(2-S-Pad1)") (class "Default")
      (node (ref "2") (pin "1") (pinfunction "S_1") (pintype "passive"))
    )
    (net (code "125") (name "unconnected-(3-P1-Pad4)") (class "Default")
      (node (ref "3") (pin "4") (pinfunction "P1_4") (pintype "passive"))
    )
    (net (code "126") (name "unconnected-(3-S-Pad1)") (class "Default")
      (node (ref "3") (pin "1") (pinfunction "S_1") (pintype "passive"))
    )
    (net (code "127") (name "unconnected-(4-P1-Pad4)") (class "Default")
      (node (ref "4") (pin "4") (pinfunction "P1_4") (pintype "passive"))
    )
    (net (code "128") (name "unconnected-(4-S-Pad1)") (class "Default")
      (node (ref "4") (pin "1") (pinfunction "S_1") (pintype "passive"))
    )
    (net (code "129") (name "unconnected-(5-P1-Pad4)") (class "Default")
      (node (ref "5") (pin "4") (pinfunction "P1_4") (pintype "passive"))
    )
    (net (code "130") (name "unconnected-(5-S-Pad1)") (class "Default")
      (node (ref "5") (pin "1") (pinfunction "S_1") (pintype "passive"))
    )
    (net (code "131") (name "unconnected-(6-P1-Pad4)") (class "Default")
      (node (ref "6") (pin "4") (pinfunction "P1_4") (pintype "passive"))
    )
    (net (code "132") (name "unconnected-(6-S-Pad1)") (class "Default")
      (node (ref "6") (pin "1") (pinfunction "S_1") (pintype "passive"))
    )
    (net (code "133") (name "unconnected-(7-P1-Pad4)") (class "Default")
      (node (ref "7") (pin "4") (pinfunction "P1_4") (pintype "passive"))
    )
    (net (code "134") (name "unconnected-(7-S-Pad1)") (class "Default")
      (node (ref "7") (pin "1") (pinfunction "S_1") (pintype "passive"))
    )
    (net (code "135") (name "unconnected-(8-P1-Pad4)") (class "Default")
      (node (ref "8") (pin "4") (pinfunction "P1_4") (pintype "passive"))
    )
    (net (code "136") (name "unconnected-(8-S-Pad1)") (class "Default")
      (node (ref "8") (pin "1") (pinfunction "S_1") (pintype "passive"))
    )
    (net (code "137") (name "unconnected-(9-P1-Pad4)") (class "Default")
      (node (ref "9") (pin "4") (pinfunction "P1_4") (pintype "passive"))
    )
    (net (code "138") (name "unconnected-(9-S-Pad1)") (class "Default")
      (node (ref "9") (pin "1") (pinfunction "S_1") (pintype "passive"))
    )
    (net (code "139") (name "unconnected-(A-P1-Pad4)") (class "Default")
      (node (ref "A") (pin "4") (pinfunction "P1_4") (pintype "passive"))
    )
    (net (code "140") (name "unconnected-(A-S-Pad1)") (class "Default")
      (node (ref "A") (pin "1") (pinfunction "S_1") (pintype "passive"))
    )
    (net (code "141") (name "unconnected-(AD-P1-Pad4)") (class "Default")
      (node (ref "AD") (pin "4") (pinfunction "P1_4") (pintype "passive"))
    )
    (net (code "142") (name "unconnected-(AD-S-Pad1)") (class "Default")
      (node (ref "AD") (pin "1") (pinfunction "S_1") (pintype "passive"))
    )
    (net (code "143") (name "unconnected-(B-P1-Pad4)") (class "Default")
      (node (ref "B") (pin "4") (pinfunction "P1_4") (pintype "passive"))
    )
    (net (code "144") (name "unconnected-(B-S-Pad1)") (class "Default")
      (node (ref "B") (pin "1") (pinfunction "S_1") (pintype "passive"))
    )
    (net (code "145") (name "unconnected-(C-P1-Pad4)") (class "Default")
      (node (ref "C") (pin "4") (pinfunction "P1_4") (pintype "passive"))
    )
    (net (code "146") (name "unconnected-(C-S-Pad1)") (class "Default")
      (node (ref "C") (pin "1") (pinfunction "S_1") (pintype "passive"))
    )
    (net (code "147") (name "unconnected-(D-P1-Pad4)") (class "Default")
      (node (ref "D") (pin "4") (pinfunction "P1_4") (pintype "passive"))
    )
    (net (code "148") (name "unconnected-(D-S-Pad1)") (class "Default")
      (node (ref "D") (pin "1") (pinfunction "S_1") (pintype "passive"))
    )
    (net (code "149") (name "unconnected-(E-P1-Pad4)") (class "Default")
      (node (ref "E") (pin "4") (pinfunction "P1_4") (pintype "passive"))
    )
    (net (code "150") (name "unconnected-(E-S-Pad1)") (class "Default")
      (node (ref "E") (pin "1") (pinfunction "S_1") (pintype "passive"))
    )
    (net (code "151") (name "unconnected-(F-P1-Pad4)") (class "Default")
      (node (ref "F") (pin "4") (pinfunction "P1_4") (pintype "passive"))
    )
    (net (code "152") (name "unconnected-(F-S-Pad1)") (class "Default")
      (node (ref "F") (pin "1") (pinfunction "S_1") (pintype "passive"))
    )
    (net (code "153") (name "unconnected-(GO-P1-Pad4)") (class "Default")
      (node (ref "GO") (pin "4") (pinfunction "P1_4") (pintype "passive"))
    )
    (net (code "154") (name "unconnected-(GO-S-Pad1)") (class "Default")
      (node (ref "GO") (pin "1") (pinfunction "S_1") (pintype "passive"))
    )
    (net (code "155") (name "unconnected-(RESET-P-Pad3)") (class "Default")
      (node (ref "RESET") (pin "3") (pinfunction "P_3") (pintype "passive"))
    )
    (net (code "156") (name "unconnected-(RESET-S-Pad1)") (class "Default")
      (node (ref "RESET") (pin "1") (pinfunction "S_1") (pintype "passive"))
    )
    (net (code "157") (name "unconnected-(SHIFT-P-Pad3)") (class "Default")
      (node (ref "SHIFT") (pin "3") (pinfunction "P_3") (pintype "passive"))
    )
    (net (code "158") (name "unconnected-(SHIFT-S-Pad1)") (class "Default")
      (node (ref "SHIFT") (pin "1") (pinfunction "S_1") (pintype "passive"))
    )
    (net (code "159") (name "unconnected-(U$6-PadD+)") (class "Default")
      (node (ref "U$6") (pin "D+") (pinfunction "D+_D+") (pintype "bidirectional"))
    )
    (net (code "160") (name "unconnected-(U$6-PadD-)") (class "Default")
      (node (ref "U$6") (pin "D-") (pinfunction "D-_D-") (pintype "bidirectional"))
    )
    (net (code "161") (name "unconnected-(U$6-SH_1-PadP$1)") (class "Default")
      (node (ref "U$6") (pin "P$1") (pinfunction "SH_1_P$1") (pintype "bidirectional"))
    )
    (net (code "162") (name "unconnected-(U$6-SH_2-PadP$2)") (class "Default")
      (node (ref "U$6") (pin "P$2") (pinfunction "SH_2_P$2") (pintype "bidirectional"))
    )
  )
)
